# device.net
KiCad netlist of a schematic drawn in EAGLE
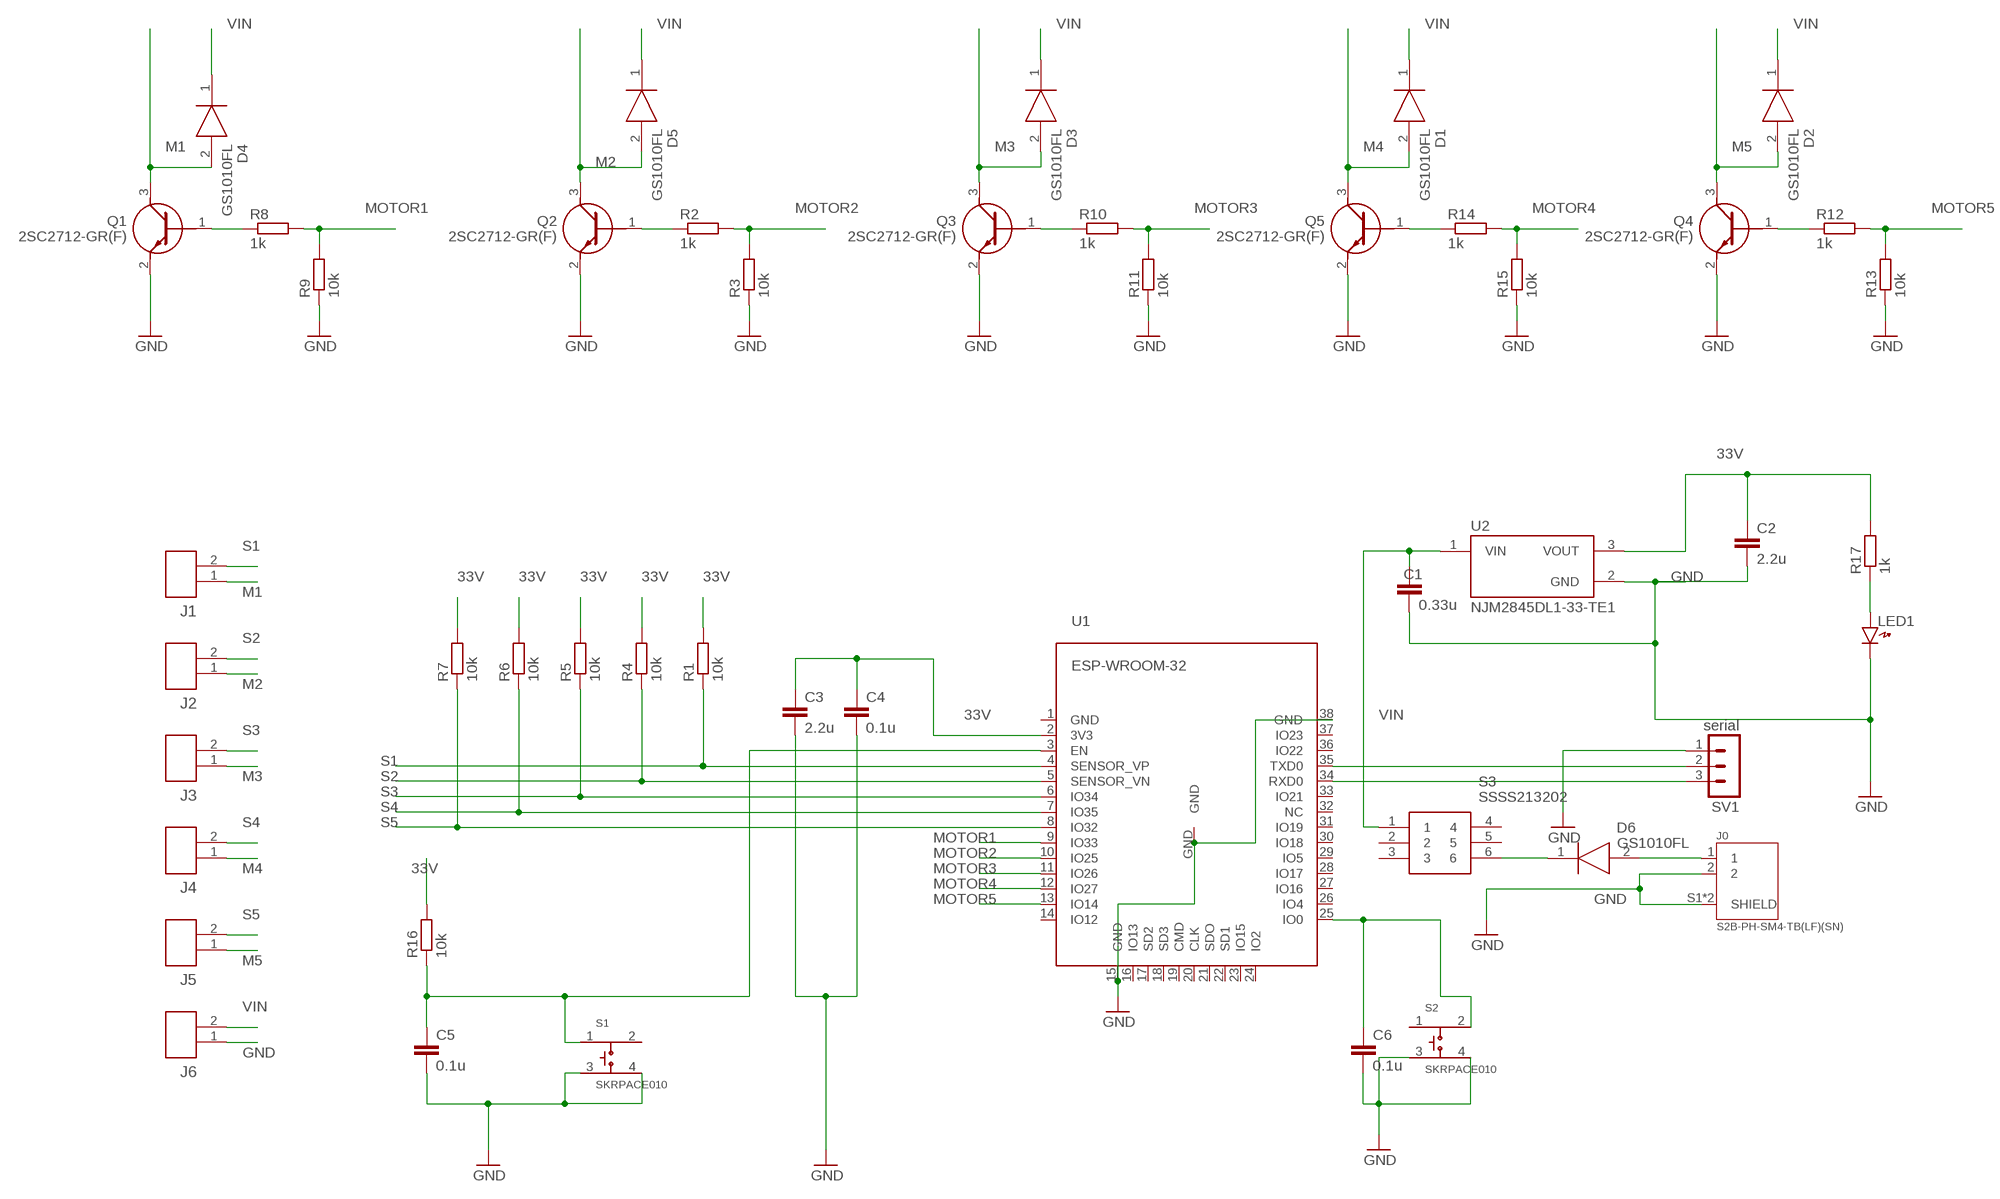
[diagram p0: schematic, sheet 1]

(export (version "E")
  (design (tool "Eeschema 10.0.6"))
  (components
    (comp (ref "C1")
      (value "0.33u")
      (footprint "eagle-import:C025-024X044")
      (libsource (lib "eagle-import") (part "C-EU025-024X044"))
    )
    (comp (ref "C2")
      (value "2.2u")
      (footprint "eagle-import:C0402")
      (libsource (lib "eagle-import") (part "C-EUC0402"))
    )
    (comp (ref "C3")
      (value "2.2u")
      (footprint "eagle-import:C0402")
      (libsource (lib "eagle-import") (part "C-EUC0402"))
    )
    (comp (ref "C4")
      (value "0.1u")
      (footprint "eagle-import:C0402")
      (libsource (lib "eagle-import") (part "C-EUC0402"))
    )
    (comp (ref "C5")
      (value "0.1u")
      (footprint "eagle-import:C0402")
      (libsource (lib "eagle-import") (part "C-EUC0402"))
    )
    (comp (ref "C6")
      (value "0.1u")
      (footprint "eagle-import:C0402")
      (libsource (lib "eagle-import") (part "C-EUC0402"))
    )
    (comp (ref "D1")
      (value "GS1010FL")
      (footprint "eagle-import:SODFL3618X110N")
      (libsource (lib "eagle-import") (part "GS1010FL"))
    )
    (comp (ref "D2")
      (value "GS1010FL")
      (footprint "eagle-import:SODFL3618X110N")
      (libsource (lib "eagle-import") (part "GS1010FL"))
    )
    (comp (ref "D3")
      (value "GS1010FL")
      (footprint "eagle-import:SODFL3618X110N")
      (libsource (lib "eagle-import") (part "GS1010FL"))
    )
    (comp (ref "D4")
      (value "GS1010FL")
      (footprint "eagle-import:SODFL3618X110N")
      (libsource (lib "eagle-import") (part "GS1010FL"))
    )
    (comp (ref "D5")
      (value "GS1010FL")
      (footprint "eagle-import:SODFL3618X110N")
      (libsource (lib "eagle-import") (part "GS1010FL"))
    )
    (comp (ref "D6")
      (value "GS1010FL")
      (footprint "eagle-import:SODFL3618X110N")
      (libsource (lib "eagle-import") (part "GS1010FL"))
    )
    (comp (ref "J0")
      (value "S2B-PH-SM4-TB(LF)(SN)")
      (footprint "eagle-import:JST_S2B-PH-SM4-TB(LF)(SN)")
      (fields
        (field (name "DIGI-KEY_PART_NUMBER") "455-1749-1-ND")
        (field (name "MF") "JST Sales")
        (field (name "MP") "S2B-PH-SM4-TB_LF__SN_")
      )
      (libsource (lib "eagle-import") (part "S2B-PH-SM4-TB(LF)(SN)"))
    )
    (comp (ref "J1")
      (value "JST_ZH_2PIN")
      (footprint "eagle-import:JST_ZH_2PIN")
      (libsource (lib "eagle-import") (part "JST_ZH_2PIN"))
    )
    (comp (ref "J2")
      (value "JST_ZH_2PIN")
      (footprint "eagle-import:JST_ZH_2PIN")
      (libsource (lib "eagle-import") (part "JST_ZH_2PIN"))
    )
    (comp (ref "J3")
      (value "JST_ZH_2PIN")
      (footprint "eagle-import:JST_ZH_2PIN")
      (libsource (lib "eagle-import") (part "JST_ZH_2PIN"))
    )
    (comp (ref "J4")
      (value "JST_ZH_2PIN")
      (footprint "eagle-import:JST_ZH_2PIN")
      (libsource (lib "eagle-import") (part "JST_ZH_2PIN"))
    )
    (comp (ref "J5")
      (value "JST_ZH_2PIN")
      (footprint "eagle-import:JST_ZH_2PIN")
      (libsource (lib "eagle-import") (part "JST_ZH_2PIN"))
    )
    (comp (ref "J6")
      (value "JST_ZH_2PIN")
      (footprint "eagle-import:JST_ZH_2PIN")
      (libsource (lib "eagle-import") (part "JST_ZH_2PIN"))
    )
    (comp (ref "LED1")
      (value "LED1608")
      (footprint "eagle-import:LED1608")
      (libsource (lib "eagle-import") (part "LED1608"))
    )
    (comp (ref "Q1")
      (value "2SC2712-GR(F)")
      (footprint "eagle-import:SC-59")
      (fields (field (name "RS_PART_NUMBER") "5319309"))
      (libsource (lib "eagle-import") (part "2SC2712-GR(F)"))
    )
    (comp (ref "Q2")
      (value "2SC2712-GR(F)")
      (footprint "eagle-import:SC-59")
      (fields (field (name "RS_PART_NUMBER") "5319309"))
      (libsource (lib "eagle-import") (part "2SC2712-GR(F)"))
    )
    (comp (ref "Q3")
      (value "2SC2712-GR(F)")
      (footprint "eagle-import:SC-59")
      (fields (field (name "RS_PART_NUMBER") "5319309"))
      (libsource (lib "eagle-import") (part "2SC2712-GR(F)"))
    )
    (comp (ref "Q4")
      (value "2SC2712-GR(F)")
      (footprint "eagle-import:SC-59")
      (fields (field (name "RS_PART_NUMBER") "5319309"))
      (libsource (lib "eagle-import") (part "2SC2712-GR(F)"))
    )
    (comp (ref "Q5")
      (value "2SC2712-GR(F)")
      (footprint "eagle-import:SC-59")
      (fields (field (name "RS_PART_NUMBER") "5319309"))
      (libsource (lib "eagle-import") (part "2SC2712-GR(F)"))
    )
    (comp (ref "R1")
      (value "10k")
      (footprint "eagle-import:R0603")
      (libsource (lib "eagle-import") (part "R-EU_R0603"))
    )
    (comp (ref "R2")
      (value "1k")
      (footprint "eagle-import:R0603")
      (libsource (lib "eagle-import") (part "R-EU_R0603"))
    )
    (comp (ref "R3")
      (value "10k")
      (footprint "eagle-import:R0603")
      (libsource (lib "eagle-import") (part "R-EU_R0603"))
    )
    (comp (ref "R4")
      (value "10k")
      (footprint "eagle-import:R0603")
      (libsource (lib "eagle-import") (part "R-EU_R0603"))
    )
    (comp (ref "R5")
      (value "10k")
      (footprint "eagle-import:R0603")
      (libsource (lib "eagle-import") (part "R-EU_R0603"))
    )
    (comp (ref "R6")
      (value "10k")
      (footprint "eagle-import:R0603")
      (libsource (lib "eagle-import") (part "R-EU_R0603"))
    )
    (comp (ref "R7")
      (value "10k")
      (footprint "eagle-import:R0603")
      (libsource (lib "eagle-import") (part "R-EU_R0603"))
    )
    (comp (ref "R8")
      (value "1k")
      (footprint "eagle-import:R0603")
      (libsource (lib "eagle-import") (part "R-EU_R0603"))
    )
    (comp (ref "R9")
      (value "10k")
      (footprint "eagle-import:R0603")
      (libsource (lib "eagle-import") (part "R-EU_R0603"))
    )
    (comp (ref "R10")
      (value "1k")
      (footprint "eagle-import:R0603")
      (libsource (lib "eagle-import") (part "R-EU_R0603"))
    )
    (comp (ref "R11")
      (value "10k")
      (footprint "eagle-import:R0603")
      (libsource (lib "eagle-import") (part "R-EU_R0603"))
    )
    (comp (ref "R12")
      (value "1k")
      (footprint "eagle-import:R0603")
      (libsource (lib "eagle-import") (part "R-EU_R0603"))
    )
    (comp (ref "R13")
      (value "10k")
      (footprint "eagle-import:R0603")
      (libsource (lib "eagle-import") (part "R-EU_R0603"))
    )
    (comp (ref "R14")
      (value "1k")
      (footprint "eagle-import:R0603")
      (libsource (lib "eagle-import") (part "R-EU_R0603"))
    )
    (comp (ref "R15")
      (value "10k")
      (footprint "eagle-import:R0603")
      (libsource (lib "eagle-import") (part "R-EU_R0603"))
    )
    (comp (ref "R16")
      (value "10k")
      (footprint "eagle-import:R0603")
      (libsource (lib "eagle-import") (part "R-EU_R0603"))
    )
    (comp (ref "R17")
      (value "1k")
      (footprint "eagle-import:R0603")
      (libsource (lib "eagle-import") (part "R-EU_R0603"))
    )
    (comp (ref "S1")
      (value "SKRPACE010")
      (footprint "eagle-import:SW_SKRPACE010")
      (fields (field (name "MF") "ALPS"))
      (libsource (lib "eagle-import") (part "SKRPACE010"))
    )
    (comp (ref "S2")
      (value "SKRPACE010")
      (footprint "eagle-import:SW_SKRPACE010")
      (fields (field (name "MF") "ALPS"))
      (libsource (lib "eagle-import") (part "SKRPACE010"))
    )
    (comp (ref "S3")
      (value "SSSS213202")
      (footprint "eagle-import:SSSS213202")
      (fields (field (name "MOUSER_PART_NUMBER") "688-SSSS213202") (field (name "RS_PART_NUMBER") "1238917"))
      (libsource (lib "eagle-import") (part "SSSS213202"))
    )
    (comp (ref "SV1")
      (value "serial")
      (footprint "eagle-import:MA03-1")
      (libsource (lib "eagle-import") (part "MA03-1"))
    )
    (comp (ref "U1")
      (value "ESP-WROOM-32")
      (footprint "eagle-import:ESP-WROOM-32")
      (libsource (lib "eagle-import") (part "ESP-WROOM-32"))
    )
    (comp (ref "U2")
      (value "NJM2845DL1-33-TE1")
      (footprint "eagle-import:DPAK228P968X238-4N")
      (fields (field (name "MF") "NJR Corporation/NJRC"))
      (libsource (lib "eagle-import") (part "NJM2845DL1-33-TE1"))
    )
  )
  (nets
    (net (code "1") (name "/33V") (class "Default")
      (node (ref "C2") (pin "1") (pinfunction "1_1") (pintype "passive"))
      (node (ref "C3") (pin "1") (pinfunction "1_1") (pintype "passive"))
      (node (ref "C4") (pin "1") (pinfunction "1_1") (pintype "passive"))
      (node (ref "R1") (pin "2") (pinfunction "2_2") (pintype "passive"))
      (node (ref "R16") (pin "2") (pinfunction "2_2") (pintype "passive"))
      (node (ref "R17") (pin "2") (pinfunction "2_2") (pintype "passive"))
      (node (ref "R4") (pin "2") (pinfunction "2_2") (pintype "passive"))
      (node (ref "R5") (pin "2") (pinfunction "2_2") (pintype "passive"))
      (node (ref "R6") (pin "2") (pinfunction "2_2") (pintype "passive"))
      (node (ref "R7") (pin "2") (pinfunction "2_2") (pintype "passive"))
      (node (ref "U1") (pin "2") (pinfunction "3V3_2") (pintype "bidirectional"))
      (node (ref "U2") (pin "3") (pinfunction "VOUT_3") (pintype "output"))
    )
    (net (code "2") (name "/M1") (class "Default")
      (node (ref "D4") (pin "2") (pinfunction "A_2") (pintype "bidirectional"))
      (node (ref "J1") (pin "1") (pinfunction "P$1_1") (pintype "bidirectional"))
      (node (ref "Q1") (pin "3") (pinfunction "C_3") (pintype "bidirectional"))
    )
    (net (code "3") (name "/M2") (class "Default")
      (node (ref "D5") (pin "2") (pinfunction "A_2") (pintype "bidirectional"))
      (node (ref "J2") (pin "1") (pinfunction "P$1_1") (pintype "bidirectional"))
      (node (ref "Q2") (pin "3") (pinfunction "C_3") (pintype "bidirectional"))
    )
    (net (code "4") (name "/M3") (class "Default")
      (node (ref "D3") (pin "2") (pinfunction "A_2") (pintype "bidirectional"))
      (node (ref "J3") (pin "1") (pinfunction "P$1_1") (pintype "bidirectional"))
      (node (ref "Q3") (pin "3") (pinfunction "C_3") (pintype "bidirectional"))
    )
    (net (code "5") (name "/M4") (class "Default")
      (node (ref "D1") (pin "2") (pinfunction "A_2") (pintype "bidirectional"))
      (node (ref "J4") (pin "1") (pinfunction "P$1_1") (pintype "bidirectional"))
      (node (ref "Q5") (pin "3") (pinfunction "C_3") (pintype "bidirectional"))
    )
    (net (code "6") (name "/M5") (class "Default")
      (node (ref "D2") (pin "2") (pinfunction "A_2") (pintype "bidirectional"))
      (node (ref "J5") (pin "1") (pinfunction "P$1_1") (pintype "bidirectional"))
      (node (ref "Q4") (pin "3") (pinfunction "C_3") (pintype "bidirectional"))
    )
    (net (code "7") (name "/MOTOR1") (class "Default")
      (node (ref "R8") (pin "2") (pinfunction "2_2") (pintype "passive"))
      (node (ref "R9") (pin "2") (pinfunction "2_2") (pintype "passive"))
      (node (ref "U1") (pin "9") (pinfunction "IO33_9") (pintype "bidirectional"))
    )
    (net (code "8") (name "/MOTOR2") (class "Default")
      (node (ref "R2") (pin "2") (pinfunction "2_2") (pintype "passive"))
      (node (ref "R3") (pin "2") (pinfunction "2_2") (pintype "passive"))
      (node (ref "U1") (pin "10") (pinfunction "IO25_10") (pintype "bidirectional"))
    )
    (net (code "9") (name "/MOTOR3") (class "Default")
      (node (ref "R10") (pin "2") (pinfunction "2_2") (pintype "passive"))
      (node (ref "R11") (pin "2") (pinfunction "2_2") (pintype "passive"))
      (node (ref "U1") (pin "11") (pinfunction "IO26_11") (pintype "bidirectional"))
    )
    (net (code "10") (name "/MOTOR4") (class "Default")
      (node (ref "R14") (pin "2") (pinfunction "2_2") (pintype "passive"))
      (node (ref "R15") (pin "2") (pinfunction "2_2") (pintype "passive"))
      (node (ref "U1") (pin "12") (pinfunction "IO27_12") (pintype "bidirectional"))
    )
    (net (code "11") (name "/MOTOR5") (class "Default")
      (node (ref "R12") (pin "2") (pinfunction "2_2") (pintype "passive"))
      (node (ref "R13") (pin "2") (pinfunction "2_2") (pintype "passive"))
      (node (ref "U1") (pin "13") (pinfunction "IO14_13") (pintype "bidirectional"))
    )
    (net (code "12") (name "/S1") (class "Default")
      (node (ref "J1") (pin "2") (pinfunction "P$2_2") (pintype "bidirectional"))
      (node (ref "R1") (pin "1") (pinfunction "1_1") (pintype "passive"))
      (node (ref "U1") (pin "4") (pinfunction "SENSOR_VP_4") (pintype "bidirectional"))
    )
    (net (code "13") (name "/S2") (class "Default")
      (node (ref "J2") (pin "2") (pinfunction "P$2_2") (pintype "bidirectional"))
      (node (ref "R4") (pin "1") (pinfunction "1_1") (pintype "passive"))
      (node (ref "U1") (pin "5") (pinfunction "SENSOR_VN_5") (pintype "bidirectional"))
    )
    (net (code "14") (name "/S3") (class "Default")
      (node (ref "J3") (pin "2") (pinfunction "P$2_2") (pintype "bidirectional"))
      (node (ref "R5") (pin "1") (pinfunction "1_1") (pintype "passive"))
      (node (ref "U1") (pin "6") (pinfunction "IO34_6") (pintype "bidirectional"))
    )
    (net (code "15") (name "/S4") (class "Default")
      (node (ref "J4") (pin "2") (pinfunction "P$2_2") (pintype "bidirectional"))
      (node (ref "R6") (pin "1") (pinfunction "1_1") (pintype "passive"))
      (node (ref "U1") (pin "7") (pinfunction "IO35_7") (pintype "bidirectional"))
    )
    (net (code "16") (name "/S5") (class "Default")
      (node (ref "J5") (pin "2") (pinfunction "P$2_2") (pintype "bidirectional"))
      (node (ref "R7") (pin "1") (pinfunction "1_1") (pintype "passive"))
      (node (ref "U1") (pin "8") (pinfunction "IO32_8") (pintype "bidirectional"))
    )
    (net (code "17") (name "/VIN") (class "Default")
      (node (ref "C1") (pin "1") (pinfunction "1_1") (pintype "passive"))
      (node (ref "D1") (pin "1") (pinfunction "K_1") (pintype "bidirectional"))
      (node (ref "D2") (pin "1") (pinfunction "K_1") (pintype "bidirectional"))
      (node (ref "D3") (pin "1") (pinfunction "K_1") (pintype "bidirectional"))
      (node (ref "D4") (pin "1") (pinfunction "K_1") (pintype "bidirectional"))
      (node (ref "D5") (pin "1") (pinfunction "K_1") (pintype "bidirectional"))
      (node (ref "J6") (pin "2") (pinfunction "P$2_2") (pintype "bidirectional"))
      (node (ref "S3") (pin "1") (pinfunction "1_1") (pintype "bidirectional"))
      (node (ref "U2") (pin "1") (pinfunction "VIN_1") (pintype "input"))
    )
    (net (code "18") (name "GND") (class "Default")
      (node (ref "C1") (pin "2") (pinfunction "2_2") (pintype "passive"))
      (node (ref "C2") (pin "2") (pinfunction "2_2") (pintype "passive"))
      (node (ref "C3") (pin "2") (pinfunction "2_2") (pintype "passive"))
      (node (ref "C4") (pin "2") (pinfunction "2_2") (pintype "passive"))
      (node (ref "C5") (pin "2") (pinfunction "2_2") (pintype "passive"))
      (node (ref "C6") (pin "2") (pinfunction "2_2") (pintype "passive"))
      (node (ref "J0") (pin "2") (pinfunction "2_2") (pintype "passive"))
      (node (ref "J0") (pin "S1") (pinfunction "SHIELD_S1") (pintype "passive"))
      (node (ref "J0") (pin "S2") (pinfunction "SHIELD_S2") (pintype "passive"))
      (node (ref "J6") (pin "1") (pinfunction "P$1_1") (pintype "bidirectional"))
      (node (ref "LED1") (pin "K") (pinfunction "K_K") (pintype "passive"))
      (node (ref "Q1") (pin "2") (pinfunction "E_2") (pintype "bidirectional"))
      (node (ref "Q2") (pin "2") (pinfunction "E_2") (pintype "bidirectional"))
      (node (ref "Q3") (pin "2") (pinfunction "E_2") (pintype "bidirectional"))
      (node (ref "Q4") (pin "2") (pinfunction "E_2") (pintype "bidirectional"))
      (node (ref "Q5") (pin "2") (pinfunction "E_2") (pintype "bidirectional"))
      (node (ref "R11") (pin "1") (pinfunction "1_1") (pintype "passive"))
      (node (ref "R13") (pin "1") (pinfunction "1_1") (pintype "passive"))
      (node (ref "R15") (pin "1") (pinfunction "1_1") (pintype "passive"))
      (node (ref "R3") (pin "1") (pinfunction "1_1") (pintype "passive"))
      (node (ref "R9") (pin "1") (pinfunction "1_1") (pintype "passive"))
      (node (ref "S1") (pin "3") (pinfunction "3_3") (pintype "bidirectional"))
      (node (ref "S1") (pin "4") (pinfunction "4_4") (pintype "bidirectional"))
      (node (ref "S2") (pin "3") (pinfunction "3_3") (pintype "bidirectional"))
      (node (ref "S2") (pin "4") (pinfunction "4_4") (pintype "bidirectional"))
      (node (ref "SV1") (pin "1") (pinfunction "1_1") (pintype "passive"))
      (node (ref "U1") (pin "15") (pinfunction "GND_15") (pintype "bidirectional"))
      (node (ref "U1") (pin "38") (pinfunction "GND_38") (pintype "bidirectional"))
      (node (ref "U1") (pin "GND") (pinfunction "GND_GND") (pintype "bidirectional"))
      (node (ref "U2") (pin "2") (pinfunction "GND_2") (pintype "power_in"))
    )
    (net (code "19") (name "Net-(D6-A)") (class "Default")
      (node (ref "D6") (pin "2") (pinfunction "A_2") (pintype "bidirectional"))
      (node (ref "J0") (pin "1") (pinfunction "1_1") (pintype "passive"))
    )
    (net (code "20") (name "Net-(D6-K)") (class "Default")
      (node (ref "D6") (pin "1") (pinfunction "K_1") (pintype "bidirectional"))
      (node (ref "S3") (pin "6") (pinfunction "6_6") (pintype "bidirectional"))
    )
    (net (code "21") (name "Net-(LED1-PadA)") (class "Default")
      (node (ref "LED1") (pin "A") (pinfunction "A_A") (pintype "passive"))
      (node (ref "R17") (pin "1") (pinfunction "1_1") (pintype "passive"))
    )
    (net (code "22") (name "Net-(Q1-B)") (class "Default")
      (node (ref "Q1") (pin "1") (pinfunction "B_1") (pintype "bidirectional"))
      (node (ref "R8") (pin "1") (pinfunction "1_1") (pintype "passive"))
    )
    (net (code "23") (name "Net-(Q2-B)") (class "Default")
      (node (ref "Q2") (pin "1") (pinfunction "B_1") (pintype "bidirectional"))
      (node (ref "R2") (pin "1") (pinfunction "1_1") (pintype "passive"))
    )
    (net (code "24") (name "Net-(Q3-B)") (class "Default")
      (node (ref "Q3") (pin "1") (pinfunction "B_1") (pintype "bidirectional"))
      (node (ref "R10") (pin "1") (pinfunction "1_1") (pintype "passive"))
    )
    (net (code "25") (name "Net-(Q4-B)") (class "Default")
      (node (ref "Q4") (pin "1") (pinfunction "B_1") (pintype "bidirectional"))
      (node (ref "R12") (pin "1") (pinfunction "1_1") (pintype "passive"))
    )
    (net (code "26") (name "Net-(Q5-B)") (class "Default")
      (node (ref "Q5") (pin "1") (pinfunction "B_1") (pintype "bidirectional"))
      (node (ref "R14") (pin "1") (pinfunction "1_1") (pintype "passive"))
    )
    (net (code "27") (name "Net-(U1-EN)") (class "Default")
      (node (ref "C5") (pin "1") (pinfunction "1_1") (pintype "passive"))
      (node (ref "R16") (pin "1") (pinfunction "1_1") (pintype "passive"))
      (node (ref "S1") (pin "1") (pinfunction "1_1") (pintype "bidirectional"))
      (node (ref "U1") (pin "3") (pinfunction "EN_3") (pintype "bidirectional"))
    )
    (net (code "28") (name "Net-(U1-IO0)") (class "Default")
      (node (ref "C6") (pin "1") (pinfunction "1_1") (pintype "passive"))
      (node (ref "S2") (pin "2") (pinfunction "2_2") (pintype "bidirectional"))
      (node (ref "U1") (pin "25") (pinfunction "IO0_25") (pintype "bidirectional"))
    )
    (net (code "29") (name "Net-(U1-RXD0)") (class "Default")
      (node (ref "SV1") (pin "3") (pinfunction "3_3") (pintype "passive"))
      (node (ref "U1") (pin "34") (pinfunction "RXD0_34") (pintype "bidirectional"))
    )
    (net (code "30") (name "Net-(U1-TXD0)") (class "Default")
      (node (ref "SV1") (pin "2") (pinfunction "2_2") (pintype "passive"))
      (node (ref "U1") (pin "35") (pinfunction "TXD0_35") (pintype "bidirectional"))
    )
    (net (code "31") (name "unconnected-(S1-Pad2)") (class "Default")
      (node (ref "S1") (pin "2") (pinfunction "2_2") (pintype "bidirectional"))
    )
    (net (code "32") (name "unconnected-(S2-Pad1)") (class "Default")
      (node (ref "S2") (pin "1") (pinfunction "1_1") (pintype "bidirectional"))
    )
    (net (code "33") (name "unconnected-(S3-Pad2)") (class "Default")
      (node (ref "S3") (pin "2") (pinfunction "2_2") (pintype "bidirectional"))
    )
    (net (code "34") (name "unconnected-(S3-Pad3)") (class "Default")
      (node (ref "S3") (pin "3") (pinfunction "3_3") (pintype "bidirectional"))
    )
    (net (code "35") (name "unconnected-(S3-Pad4)") (class "Default")
      (node (ref "S3") (pin "4") (pinfunction "4_4") (pintype "bidirectional"))
    )
    (net (code "36") (name "unconnected-(S3-Pad5)") (class "Default")
      (node (ref "S3") (pin "5") (pinfunction "5_5") (pintype "bidirectional"))
    )
    (net (code "37") (name "unconnected-(U1-CLK-Pad20)") (class "Default")
      (node (ref "U1") (pin "20") (pinfunction "CLK_20") (pintype "bidirectional"))
    )
    (net (code "38") (name "unconnected-(U1-CMD-Pad19)") (class "Default")
      (node (ref "U1") (pin "19") (pinfunction "CMD_19") (pintype "bidirectional"))
    )
    (net (code "39") (name "unconnected-(U1-GND-Pad1)") (class "Default")
      (node (ref "U1") (pin "1") (pinfunction "GND_1") (pintype "bidirectional"))
    )
    (net (code "40") (name "unconnected-(U1-IO2-Pad24)") (class "Default")
      (node (ref "U1") (pin "24") (pinfunction "IO2_24") (pintype "bidirectional"))
    )
    (net (code "41") (name "unconnected-(U1-IO4-Pad26)") (class "Default")
      (node (ref "U1") (pin "26") (pinfunction "IO4_26") (pintype "bidirectional"))
    )
    (net (code "42") (name "unconnected-(U1-IO5-Pad29)") (class "Default")
      (node (ref "U1") (pin "29") (pinfunction "IO5_29") (pintype "bidirectional"))
    )
    (net (code "43") (name "unconnected-(U1-IO12-Pad14)") (class "Default")
      (node (ref "U1") (pin "14") (pinfunction "IO12_14") (pintype "bidirectional"))
    )
    (net (code "44") (name "unconnected-(U1-IO13-Pad16)") (class "Default")
      (node (ref "U1") (pin "16") (pinfunction "IO13_16") (pintype "bidirectional"))
    )
    (net (code "45") (name "unconnected-(U1-IO15-Pad23)") (class "Default")
      (node (ref "U1") (pin "23") (pinfunction "IO15_23") (pintype "bidirectional"))
    )
    (net (code "46") (name "unconnected-(U1-IO16-Pad27)") (class "Default")
      (node (ref "U1") (pin "27") (pinfunction "IO16_27") (pintype "bidirectional"))
    )
    (net (code "47") (name "unconnected-(U1-IO17-Pad28)") (class "Default")
      (node (ref "U1") (pin "28") (pinfunction "IO17_28") (pintype "bidirectional"))
    )
    (net (code "48") (name "unconnected-(U1-IO18-Pad30)") (class "Default")
      (node (ref "U1") (pin "30") (pinfunction "IO18_30") (pintype "bidirectional"))
    )
    (net (code "49") (name "unconnected-(U1-IO19-Pad31)") (class "Default")
      (node (ref "U1") (pin "31") (pinfunction "IO19_31") (pintype "bidirectional"))
    )
    (net (code "50") (name "unconnected-(U1-IO21-Pad33)") (class "Default")
      (node (ref "U1") (pin "33") (pinfunction "IO21_33") (pintype "bidirectional"))
    )
    (net (code "51") (name "unconnected-(U1-IO22-Pad36)") (class "Default")
      (node (ref "U1") (pin "36") (pinfunction "IO22_36") (pintype "bidirectional"))
    )
    (net (code "52") (name "unconnected-(U1-IO23-Pad37)") (class "Default")
      (node (ref "U1") (pin "37") (pinfunction "IO23_37") (pintype "bidirectional"))
    )
    (net (code "53") (name "unconnected-(U1-NC-Pad32)") (class "Default")
      (node (ref "U1") (pin "32") (pinfunction "NC_32") (pintype "bidirectional"))
    )
    (net (code "54") (name "unconnected-(U1-SD1-Pad22)") (class "Default")
      (node (ref "U1") (pin "22") (pinfunction "SD1_22") (pintype "bidirectional"))
    )
    (net (code "55") (name "unconnected-(U1-SD2-Pad17)") (class "Default")
      (node (ref "U1") (pin "17") (pinfunction "SD2_17") (pintype "bidirectional"))
    )
    (net (code "56") (name "unconnected-(U1-SD3-Pad18)") (class "Default")
      (node (ref "U1") (pin "18") (pinfunction "SD3_18") (pintype "bidirectional"))
    )
    (net (code "57") (name "unconnected-(U1-SDO-Pad21)") (class "Default")
      (node (ref "U1") (pin "21") (pinfunction "SDO_21") (pintype "bidirectional"))
    )
  )
)
